# V-00756-00.net
KiCad netlist of a schematic drawn in EAGLE
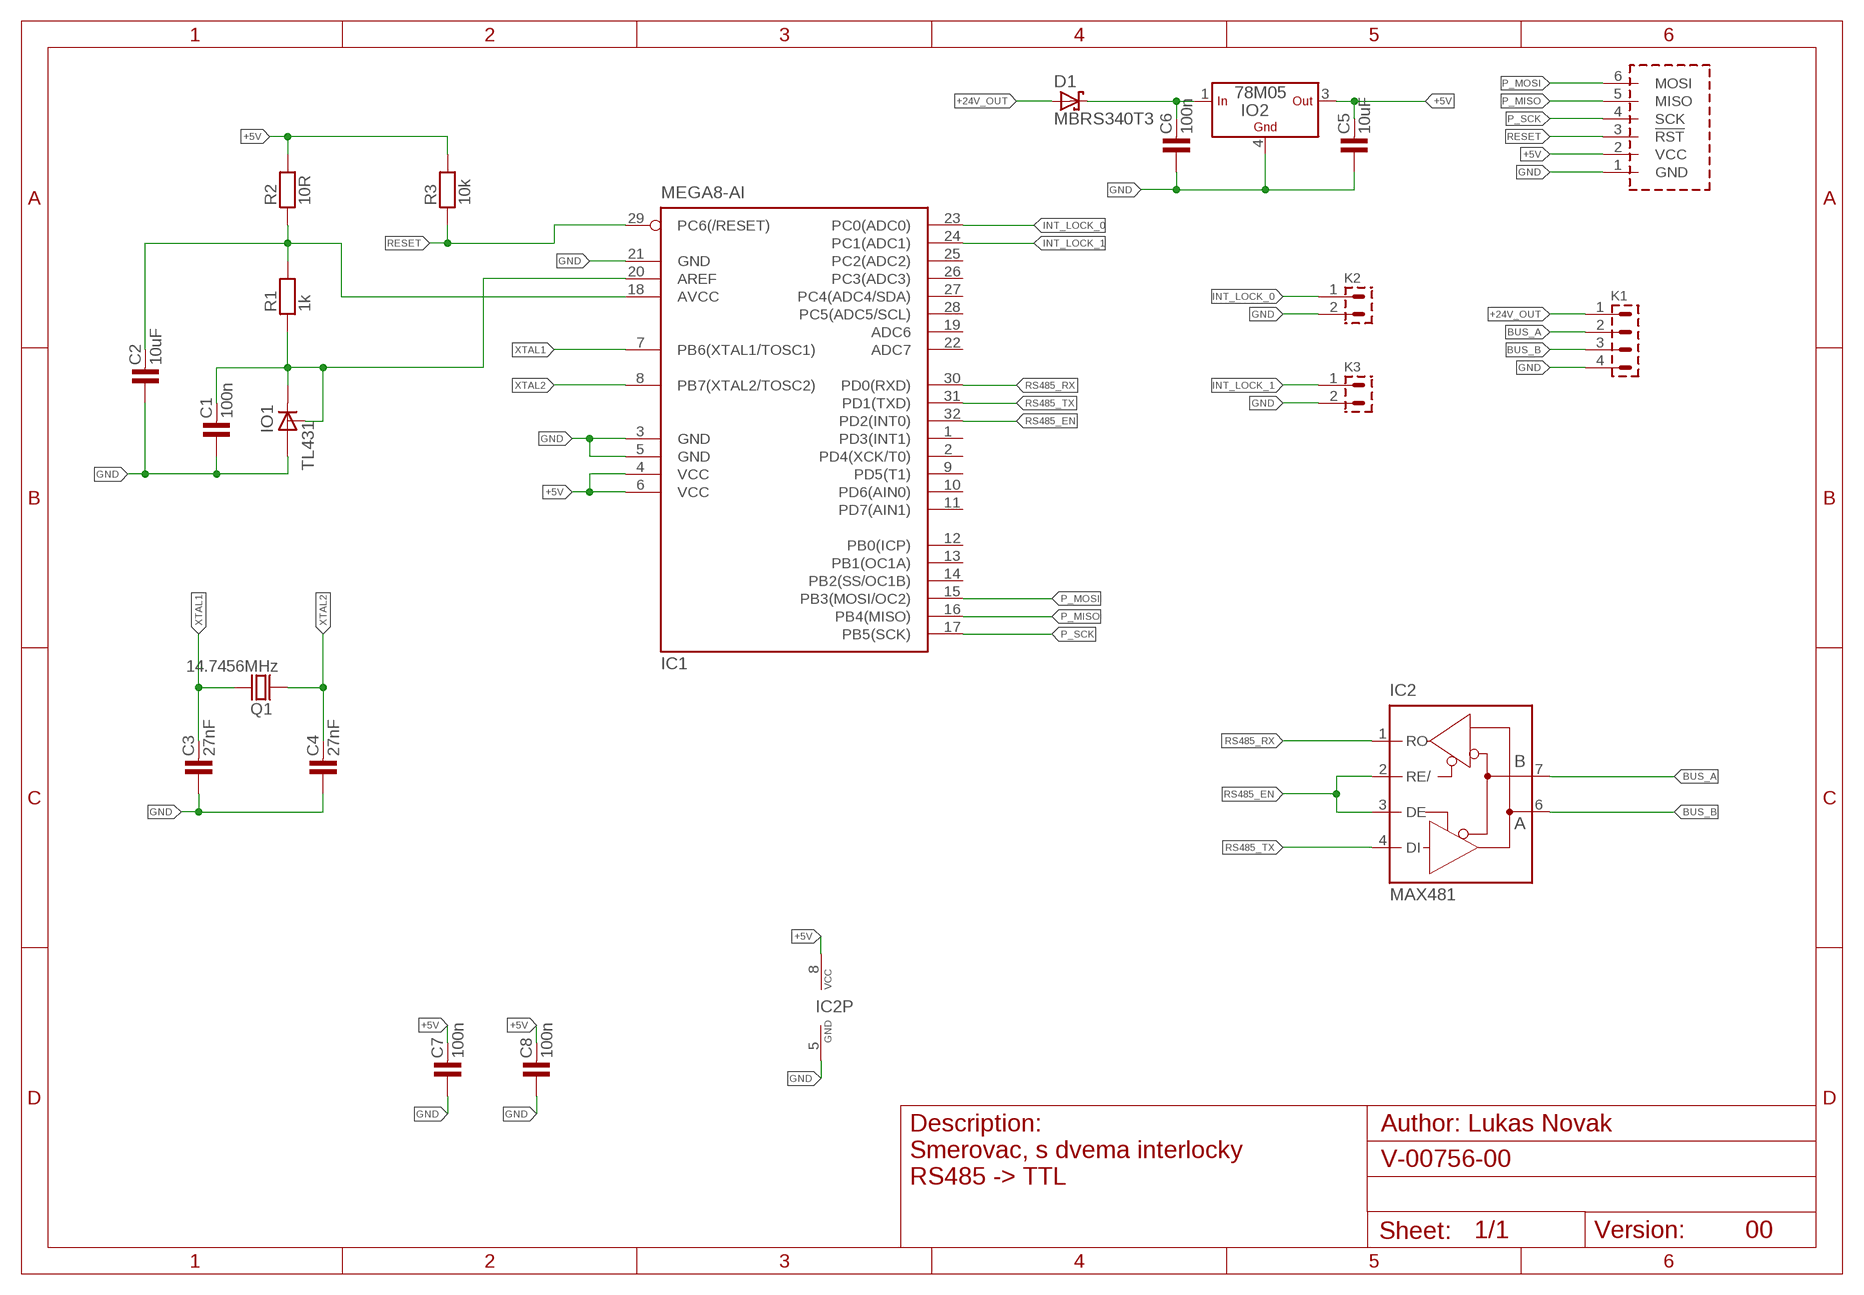
[diagram p0: schematic, sheet 1]

(export (version "E")
  (design (tool "Eeschema 10.0.6"))
  (components
    (comp (ref "C1")
      (value "100n")
      (footprint "eagle-import:1206")
      (libsource (lib "eagle-import") (part "C-KER_1206"))
    )
    (comp (ref "C2")
      (value "10uF")
      (footprint "eagle-import:1206")
      (libsource (lib "eagle-import") (part "C-KER_1206"))
    )
    (comp (ref "C3")
      (value "27nF")
      (footprint "eagle-import:0805")
      (libsource (lib "eagle-import") (part "C-KER_0805"))
    )
    (comp (ref "C4")
      (value "27nF")
      (footprint "eagle-import:0805")
      (libsource (lib "eagle-import") (part "C-KER_0805"))
    )
    (comp (ref "C5")
      (value "10uF")
      (footprint "eagle-import:1206")
      (libsource (lib "eagle-import") (part "C-KER_1206"))
    )
    (comp (ref "C6")
      (value "100n")
      (footprint "eagle-import:1206")
      (libsource (lib "eagle-import") (part "C-KER_1206"))
    )
    (comp (ref "C7")
      (value "100n")
      (footprint "eagle-import:1206")
      (libsource (lib "eagle-import") (part "C-KER_1206"))
    )
    (comp (ref "C8")
      (value "100n")
      (footprint "eagle-import:1206")
      (libsource (lib "eagle-import") (part "C-KER_1206"))
    )
    (comp (ref "D1")
      (value "MBRS340T3")
      (footprint "eagle-import:SMC")
      (libsource (lib "eagle-import") (part "MBRS30T34"))
    )
    (comp (ref "IC1")
      (value "MEGA8-AI")
      (footprint "eagle-import:TQFP32-08")
      (fields (field (name "MPN") "ATMEGA8-16AU"))
      (libsource (lib "eagle-import") (part "MEGA8-AI"))
    )
    (comp (ref "IC2")
      (value "MAX481")
      (footprint "eagle-import:SO08")
      (fields (field (name "MF") "MAXIM") (field (name "MPN") "MAX481CSA"))
      (libsource (lib "eagle-import") (part "MAX481CSA"))
    )
    (comp (ref "IO1")
      (value "TL431")
      (footprint "eagle-import:SOT23")
      (fields (field (name "MPN") "TL431BFDT"))
      (libsource (lib "eagle-import") (part "TL431SOT23"))
    )
    (comp (ref "IO2")
      (value "78M05")
      (footprint "eagle-import:DPAK")
      (libsource (lib "eagle-import") (part "LF_CDT"))
    )
    (comp (ref "K1")
      (value "PSH02-04W")
      (footprint "eagle-import:PSH02-04W")
      (libsource (lib "eagle-import") (part "PSH02-04W"))
    )
    (comp (ref "K2")
      (value "PSH02-02W")
      (footprint "eagle-import:PSH02-02W")
      (libsource (lib "eagle-import") (part "PSH02-02W"))
    )
    (comp (ref "K3")
      (value "PSH02-02W")
      (footprint "eagle-import:PSH02-02W")
      (libsource (lib "eagle-import") (part "PSH02-02W"))
    )
    (comp (ref "Q1")
      (value "14.7456MHz")
      (footprint "eagle-import:HC-49U")
      (libsource (lib "eagle-import") (part "Q_HC-49U"))
    )
    (comp (ref "R1")
      (value "1k")
      (footprint "eagle-import:1206")
      (libsource (lib "eagle-import") (part "R_1206"))
    )
    (comp (ref "R2")
      (value "10R")
      (footprint "eagle-import:1206")
      (libsource (lib "eagle-import") (part "R_1206"))
    )
    (comp (ref "R3")
      (value "10k")
      (footprint "eagle-import:1206")
      (libsource (lib "eagle-import") (part "R_1206"))
    )
    (comp (ref "U$1")
      (value "AVR_PROG_SPI")
      (footprint "eagle-import:PSH02-06P")
      (libsource (lib "eagle-import") (part "AVR_PROG_SPI"))
    )
  )
  (nets
    (net (code "1") (name "+5V") (class "Default")
      (node (ref "C5") (pin "2") (pinfunction "2_2") (pintype "passive"))
      (node (ref "C7") (pin "2") (pinfunction "2_2") (pintype "passive"))
      (node (ref "C8") (pin "2") (pinfunction "2_2") (pintype "passive"))
      (node (ref "IC1") (pin "4") (pinfunction "VCC_4") (pintype "power_in"))
      (node (ref "IC1") (pin "6") (pinfunction "VCC_6") (pintype "power_in"))
      (node (ref "IC2") (pin "8") (pinfunction "VCC_8") (pintype "power_in"))
      (node (ref "IO2") (pin "3") (pinfunction "OUT_3") (pintype "passive"))
      (node (ref "R2") (pin "2") (pinfunction "2_2") (pintype "passive"))
      (node (ref "R3") (pin "2") (pinfunction "2_2") (pintype "passive"))
      (node (ref "U$1") (pin "2") (pinfunction "VCC_2") (pintype "bidirectional"))
    )
    (net (code "2") (name "+24V_OUT") (class "Default")
      (node (ref "D1") (pin "A") (pinfunction "A_A") (pintype "passive"))
      (node (ref "K1") (pin "1") (pinfunction "1_1") (pintype "passive"))
    )
    (net (code "3") (name "BUS_A") (class "Default")
      (node (ref "IC2") (pin "7") (pinfunction "B_7") (pintype "passive"))
      (node (ref "K1") (pin "2") (pinfunction "2_2") (pintype "passive"))
    )
    (net (code "4") (name "BUS_B") (class "Default")
      (node (ref "IC2") (pin "6") (pinfunction "A_6") (pintype "passive"))
      (node (ref "K1") (pin "3") (pinfunction "3_3") (pintype "passive"))
    )
    (net (code "5") (name "GND") (class "Default")
      (node (ref "C1") (pin "1") (pinfunction "1_1") (pintype "passive"))
      (node (ref "C2") (pin "1") (pinfunction "1_1") (pintype "passive"))
      (node (ref "C3") (pin "1") (pinfunction "1_1") (pintype "passive"))
      (node (ref "C4") (pin "1") (pinfunction "1_1") (pintype "passive"))
      (node (ref "C5") (pin "1") (pinfunction "1_1") (pintype "passive"))
      (node (ref "C6") (pin "1") (pinfunction "1_1") (pintype "passive"))
      (node (ref "C7") (pin "1") (pinfunction "1_1") (pintype "passive"))
      (node (ref "C8") (pin "1") (pinfunction "1_1") (pintype "passive"))
      (node (ref "IC1") (pin "21") (pinfunction "GND_21") (pintype "power_in"))
      (node (ref "IC1") (pin "3") (pinfunction "GND_3") (pintype "power_in"))
      (node (ref "IC1") (pin "5") (pinfunction "GND_5") (pintype "power_in"))
      (node (ref "IC2") (pin "5") (pinfunction "GND_5") (pintype "power_in"))
      (node (ref "IO1") (pin "3") (pinfunction "A_3") (pintype "bidirectional"))
      (node (ref "IO2") (pin "4") (pinfunction "GND_4") (pintype "passive"))
      (node (ref "K1") (pin "4") (pinfunction "4_4") (pintype "passive"))
      (node (ref "K2") (pin "2") (pinfunction "2_2") (pintype "passive"))
      (node (ref "K3") (pin "2") (pinfunction "2_2") (pintype "passive"))
      (node (ref "U$1") (pin "1") (pinfunction "GND_1") (pintype "bidirectional"))
    )
    (net (code "6") (name "INT_LOCK_0") (class "Default")
      (node (ref "IC1") (pin "23") (pinfunction "PC0(ADC0)_23") (pintype "bidirectional"))
      (node (ref "K2") (pin "1") (pinfunction "1_1") (pintype "passive"))
    )
    (net (code "7") (name "INT_LOCK_1") (class "Default")
      (node (ref "IC1") (pin "24") (pinfunction "PC1(ADC1)_24") (pintype "bidirectional"))
      (node (ref "K3") (pin "1") (pinfunction "1_1") (pintype "passive"))
    )
    (net (code "8") (name "Net-(IC1-AREF)") (class "Default")
      (node (ref "C1") (pin "2") (pinfunction "2_2") (pintype "passive"))
      (node (ref "IC1") (pin "20") (pinfunction "AREF_20") (pintype "passive"))
      (node (ref "IO1") (pin "1") (pinfunction "C_1") (pintype "bidirectional"))
      (node (ref "IO1") (pin "2") (pinfunction "R_2") (pintype "bidirectional"))
      (node (ref "R1") (pin "1") (pinfunction "1_1") (pintype "passive"))
    )
    (net (code "9") (name "Net-(IC1-AVCC)") (class "Default")
      (node (ref "C2") (pin "2") (pinfunction "2_2") (pintype "passive"))
      (node (ref "IC1") (pin "18") (pinfunction "AVCC_18") (pintype "power_in"))
      (node (ref "R1") (pin "2") (pinfunction "2_2") (pintype "passive"))
      (node (ref "R2") (pin "1") (pinfunction "1_1") (pintype "passive"))
    )
    (net (code "10") (name "Net-(IO2-IN)") (class "Default")
      (node (ref "C6") (pin "2") (pinfunction "2_2") (pintype "passive"))
      (node (ref "D1") (pin "C") (pinfunction "C_C") (pintype "passive"))
      (node (ref "IO2") (pin "1") (pinfunction "IN_1") (pintype "passive"))
    )
    (net (code "11") (name "P_MISO") (class "Default")
      (node (ref "IC1") (pin "16") (pinfunction "PB4(MISO)_16") (pintype "bidirectional"))
      (node (ref "U$1") (pin "5") (pinfunction "MISO_5") (pintype "bidirectional"))
    )
    (net (code "12") (name "P_MOSI") (class "Default")
      (node (ref "IC1") (pin "15") (pinfunction "PB3(MOSI/OC2)_15") (pintype "bidirectional"))
      (node (ref "U$1") (pin "6") (pinfunction "MOSI_6") (pintype "bidirectional"))
    )
    (net (code "13") (name "P_SCK") (class "Default")
      (node (ref "IC1") (pin "17") (pinfunction "PB5(SCK)_17") (pintype "bidirectional"))
      (node (ref "U$1") (pin "4") (pinfunction "SCK_4") (pintype "bidirectional"))
    )
    (net (code "14") (name "RESET") (class "Default")
      (node (ref "IC1") (pin "29") (pinfunction "PC6(/RESET)_29") (pintype "bidirectional"))
      (node (ref "R3") (pin "1") (pinfunction "1_1") (pintype "passive"))
      (node (ref "U$1") (pin "3") (pinfunction "~{RST}_3") (pintype "bidirectional"))
    )
    (net (code "15") (name "RS485_EN") (class "Default")
      (node (ref "IC1") (pin "32") (pinfunction "PD2(INT0)_32") (pintype "bidirectional"))
      (node (ref "IC2") (pin "2") (pinfunction "RE/_2") (pintype "input"))
      (node (ref "IC2") (pin "3") (pinfunction "DE_3") (pintype "input"))
    )
    (net (code "16") (name "RS485_RX") (class "Default")
      (node (ref "IC1") (pin "30") (pinfunction "PD0(RXD)_30") (pintype "bidirectional"))
      (node (ref "IC2") (pin "1") (pinfunction "RO_1") (pintype "output"))
    )
    (net (code "17") (name "RS485_TX") (class "Default")
      (node (ref "IC1") (pin "31") (pinfunction "PD1(TXD)_31") (pintype "bidirectional"))
      (node (ref "IC2") (pin "4") (pinfunction "DI_4") (pintype "input"))
    )
    (net (code "18") (name "XTAL1") (class "Default")
      (node (ref "C3") (pin "2") (pinfunction "2_2") (pintype "passive"))
      (node (ref "IC1") (pin "7") (pinfunction "PB6(XTAL1/TOSC1)_7") (pintype "bidirectional"))
      (node (ref "Q1") (pin "2") (pinfunction "2_2") (pintype "passive"))
    )
    (net (code "19") (name "XTAL2") (class "Default")
      (node (ref "C4") (pin "2") (pinfunction "2_2") (pintype "passive"))
      (node (ref "IC1") (pin "8") (pinfunction "PB7(XTAL2/TOSC2)_8") (pintype "bidirectional"))
      (node (ref "Q1") (pin "1") (pinfunction "1_1") (pintype "passive"))
    )
    (net (code "20") (name "unconnected-(IC1-ADC6-Pad19)") (class "Default")
      (node (ref "IC1") (pin "19") (pinfunction "ADC6_19") (pintype "bidirectional"))
    )
    (net (code "21") (name "unconnected-(IC1-ADC7-Pad22)") (class "Default")
      (node (ref "IC1") (pin "22") (pinfunction "ADC7_22") (pintype "bidirectional"))
    )
    (net (code "22") (name "unconnected-(IC1-PB0(ICP)-Pad12)") (class "Default")
      (node (ref "IC1") (pin "12") (pinfunction "PB0(ICP)_12") (pintype "bidirectional"))
    )
    (net (code "23") (name "unconnected-(IC1-PB1(OC1A)-Pad13)") (class "Default")
      (node (ref "IC1") (pin "13") (pinfunction "PB1(OC1A)_13") (pintype "bidirectional"))
    )
    (net (code "24") (name "unconnected-(IC1-PB2(SS{slash}OC1B)-Pad14)") (class "Default")
      (node (ref "IC1") (pin "14") (pinfunction "PB2(SS/OC1B)_14") (pintype "bidirectional"))
    )
    (net (code "25") (name "unconnected-(IC1-PC2(ADC2)-Pad25)") (class "Default")
      (node (ref "IC1") (pin "25") (pinfunction "PC2(ADC2)_25") (pintype "bidirectional"))
    )
    (net (code "26") (name "unconnected-(IC1-PC3(ADC3)-Pad26)") (class "Default")
      (node (ref "IC1") (pin "26") (pinfunction "PC3(ADC3)_26") (pintype "bidirectional"))
    )
    (net (code "27") (name "unconnected-(IC1-PC4(ADC4{slash}SDA)-Pad27)") (class "Default")
      (node (ref "IC1") (pin "27") (pinfunction "PC4(ADC4/SDA)_27") (pintype "bidirectional"))
    )
    (net (code "28") (name "unconnected-(IC1-PC5(ADC5{slash}SCL)-Pad28)") (class "Default")
      (node (ref "IC1") (pin "28") (pinfunction "PC5(ADC5/SCL)_28") (pintype "bidirectional"))
    )
    (net (code "29") (name "unconnected-(IC1-PD3(INT1)-Pad1)") (class "Default")
      (node (ref "IC1") (pin "1") (pinfunction "PD3(INT1)_1") (pintype "bidirectional"))
    )
    (net (code "30") (name "unconnected-(IC1-PD4(XCK{slash}T0)-Pad2)") (class "Default")
      (node (ref "IC1") (pin "2") (pinfunction "PD4(XCK/T0)_2") (pintype "bidirectional"))
    )
    (net (code "31") (name "unconnected-(IC1-PD5(T1)-Pad9)") (class "Default")
      (node (ref "IC1") (pin "9") (pinfunction "PD5(T1)_9") (pintype "bidirectional"))
    )
    (net (code "32") (name "unconnected-(IC1-PD6(AIN0)-Pad10)") (class "Default")
      (node (ref "IC1") (pin "10") (pinfunction "PD6(AIN0)_10") (pintype "bidirectional"))
    )
    (net (code "33") (name "unconnected-(IC1-PD7(AIN1)-Pad11)") (class "Default")
      (node (ref "IC1") (pin "11") (pinfunction "PD7(AIN1)_11") (pintype "bidirectional"))
    )
  )
)
